# Digital_Interfaces.net
KiCad netlist of a schematic drawn in Altium Designer
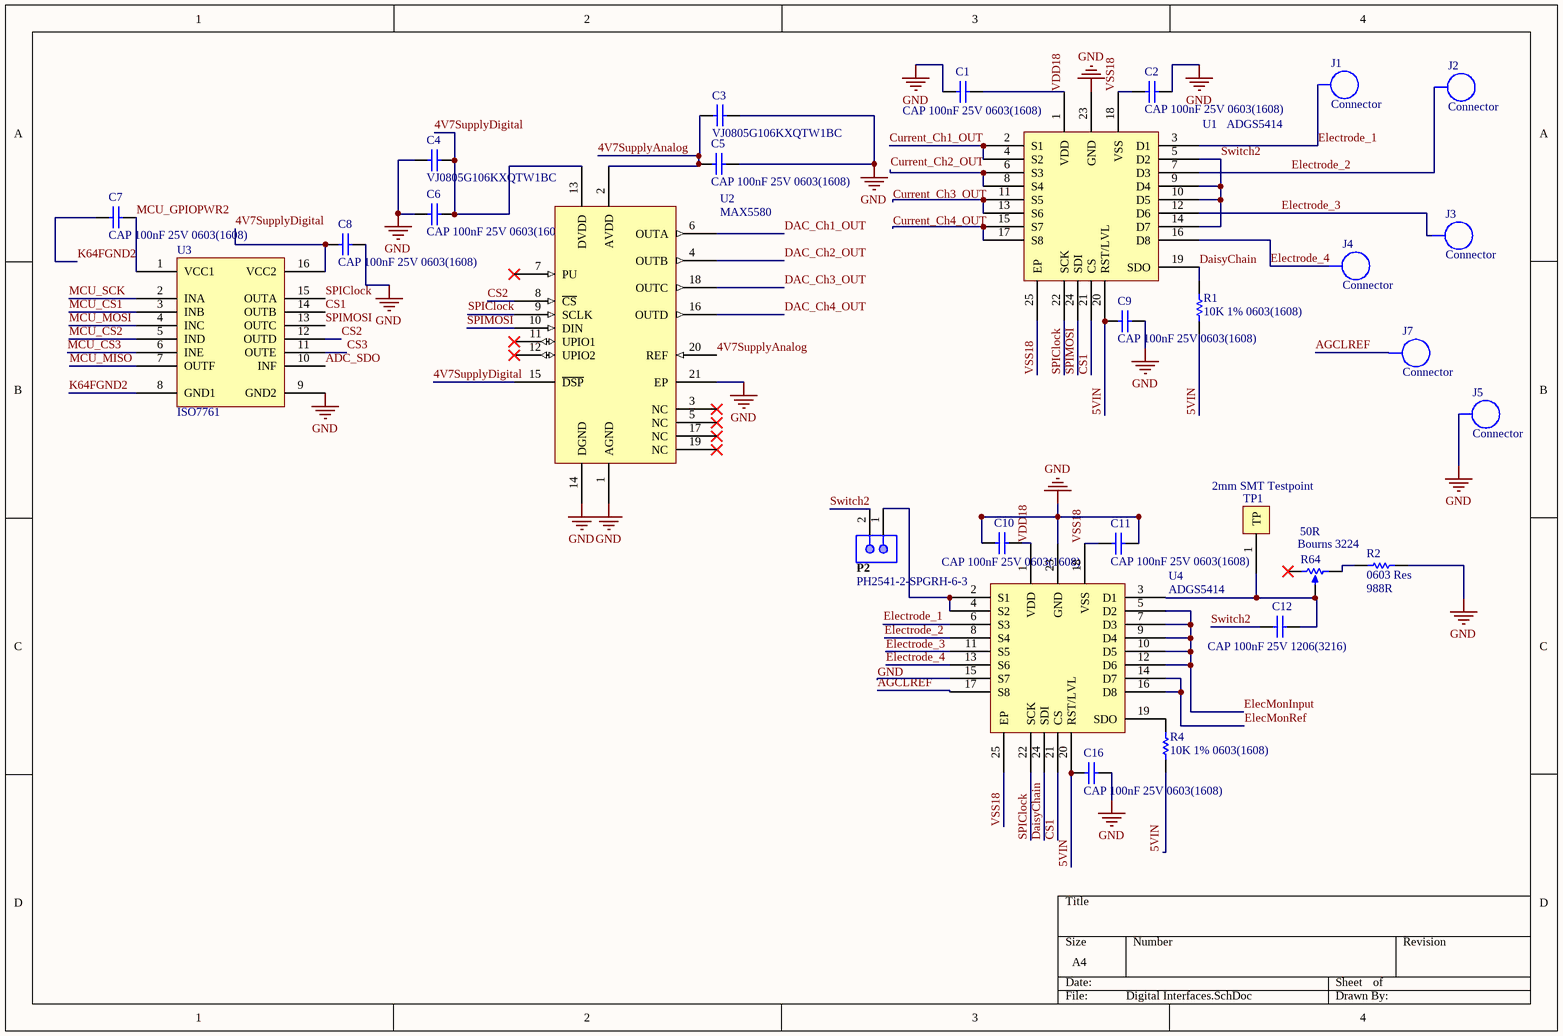
[diagram p0: Digital Interfaces.SchDoc]

(export (version "E")
  (design (tool "Eeschema 10.0.6"))
  (components
    (comp (ref "C1")
      (value "CAP 100nF 25V 0603(1608)")
      (footprint "CAPC0603(1608)100_N")
      (description "CAP 100nF 25V ±20% 0603 (1608 Metric) Thickness 1mm SMD")
      (fields (field (name "TOLERANCE") "Â±20%"))
      (libsource (lib "Altium Content Vault") (part "CAP"))
    )
    (comp (ref "C2")
      (value "CAP 100nF 25V 0603(1608)")
      (footprint "CAPC0603(1608)100_N")
      (description "CAP 100nF 25V ±20% 0603 (1608 Metric) Thickness 1mm SMD")
      (fields (field (name "TOLERANCE") "Â±20%"))
      (libsource (lib "Altium Content Vault") (part "CAP"))
    )
    (comp (ref "C3")
      (value "VJ0805G106KXQTW1BC")
      (footprint "CAPC2013X145X50LL20T20")
      (description "Chip Capacitor, 10 uF, +/- 10%, 10 V, -55 to 85 degC, 0805 (2012 Metric), RoHS, Tape and Reel")
      (fields (field (name "MANUFACTURER") "Vishay") (field (name "TOLERANCE") "10%"))
      (libsource (lib "Altium Content Vault") (part "CAP-NP-2"))
    )
    (comp (ref "C4")
      (value "VJ0805G106KXQTW1BC")
      (footprint "CAPC2013X145X50LL20T20")
      (description "Chip Capacitor, 10 uF, +/- 10%, 10 V, -55 to 85 degC, 0805 (2012 Metric), RoHS, Tape and Reel")
      (fields (field (name "MANUFACTURER") "Vishay") (field (name "TOLERANCE") "10%"))
      (libsource (lib "Altium Content Vault") (part "CAP-NP-2"))
    )
    (comp (ref "C5")
      (value "CAP 100nF 25V 0603(1608)")
      (footprint "CAPC0603(1608)100_N")
      (description "CAP 100nF 25V ±20% 0603 (1608 Metric) Thickness 1mm SMD")
      (fields (field (name "TOLERANCE") "Â±20%"))
      (libsource (lib "Altium Content Vault") (part "CAP"))
    )
    (comp (ref "C6")
      (value "CAP 100nF 25V 0603(1608)")
      (footprint "CAPC0603(1608)100_N")
      (description "CAP 100nF 25V ±20% 0603 (1608 Metric) Thickness 1mm SMD")
      (fields (field (name "TOLERANCE") "Â±20%"))
      (libsource (lib "Altium Content Vault") (part "CAP"))
    )
    (comp (ref "C7")
      (value "CAP 100nF 25V 0603(1608)")
      (footprint "CAPC0603(1608)100_N")
      (description "CAP 100nF 25V ±20% 0603 (1608 Metric) Thickness 1mm SMD")
      (fields (field (name "TOLERANCE") "Â±20%"))
      (libsource (lib "Altium Content Vault") (part "CAP"))
    )
    (comp (ref "C8")
      (value "CAP 100nF 25V 0603(1608)")
      (footprint "CAPC0603(1608)100_N")
      (description "CAP 100nF 25V ±20% 0603 (1608 Metric) Thickness 1mm SMD")
      (fields (field (name "TOLERANCE") "Â±20%"))
      (libsource (lib "Altium Content Vault") (part "CAP"))
    )
    (comp (ref "C9")
      (value "CAP 100nF 25V 0603(1608)")
      (footprint "CAPC0603(1608)100_N")
      (description "CAP 100nF 25V ±20% 0603 (1608 Metric) Thickness 1mm SMD")
      (fields (field (name "TOLERANCE") "Â±20%"))
      (libsource (lib "Altium Content Vault") (part "CAP"))
    )
    (comp (ref "C10")
      (value "CAP 100nF 25V 0603(1608)")
      (footprint "CAPC0603(1608)100_N")
      (description "CAP 100nF 25V ±20% 0603 (1608 Metric) Thickness 1mm SMD")
      (fields (field (name "TOLERANCE") "Â±20%"))
      (libsource (lib "Altium Content Vault") (part "CAP"))
    )
    (comp (ref "C11")
      (value "CAP 100nF 25V 0603(1608)")
      (footprint "CAPC0603(1608)100_N")
      (description "CAP 100nF 25V ±20% 0603 (1608 Metric) Thickness 1mm SMD")
      (fields (field (name "TOLERANCE") "Â±20%"))
      (libsource (lib "Altium Content Vault") (part "CAP"))
    )
    (comp (ref "C12")
      (value "CAP 100nF 25V 1206(3216)")
      (footprint "CAPC1206(3216)190_M")
      (description "CAP 100nF 25V ±5% 1206 (3216 Metric) Thickness 1.9mm SMD")
      (fields (field (name "TOLERANCE") "Â±5%"))
      (libsource (lib "Altium Content Vault") (part "CAP"))
    )
    (comp (ref "C16")
      (value "CAP 100nF 25V 0603(1608)")
      (footprint "CAPC0603(1608)100_N")
      (description "CAP 100nF 25V ±20% 0603 (1608 Metric) Thickness 1mm SMD")
      (fields (field (name "TOLERANCE") "Â±20%"))
      (libsource (lib "Altium Content Vault") (part "CAP"))
    )
    (comp (ref "J1")
      (value "Connector")
      (footprint "Molex TermiMate Plug")
      (description "Molex TermiMate Plug/Receptacle, 1-way SMD Board to Board or Wire to Board Connector")
      (libsource (lib "ar5113_Altium_Library") (part "Molex TermiMate"))
    )
    (comp (ref "J2")
      (value "Connector")
      (footprint "Molex TermiMate Plug")
      (description "Molex TermiMate Plug/Receptacle, 1-way SMD Board to Board or Wire to Board Connector")
      (libsource (lib "ar5113_Altium_Library") (part "Molex TermiMate"))
    )
    (comp (ref "J3")
      (value "Connector")
      (footprint "Molex TermiMate Plug")
      (description "Molex TermiMate Plug/Receptacle, 1-way SMD Board to Board or Wire to Board Connector")
      (libsource (lib "ar5113_Altium_Library") (part "Molex TermiMate"))
    )
    (comp (ref "J4")
      (value "Connector")
      (footprint "Molex TermiMate Plug")
      (description "Molex TermiMate Plug/Receptacle, 1-way SMD Board to Board or Wire to Board Connector")
      (libsource (lib "ar5113_Altium_Library") (part "Molex TermiMate"))
    )
    (comp (ref "J5")
      (value "Connector")
      (footprint "Molex TermiMate Plug")
      (description "Molex TermiMate Plug/Receptacle, 1-way SMD Board to Board or Wire to Board Connector")
      (libsource (lib "ar5113_Altium_Library") (part "Molex TermiMate"))
    )
    (comp (ref "J7")
      (value "Connector")
      (footprint "Molex TermiMate Plug")
      (description "Molex TermiMate Plug/Receptacle, 1-way SMD Board to Board or Wire to Board Connector")
      (libsource (lib "ar5113_Altium_Library") (part "Molex TermiMate"))
    )
    (comp (ref "P2")
      (value "PH2541-2-SPGRH-6-3")
      (footprint "PH2541-2-SPGRH-6-3_V")
      (description "Male Header, Pitch 2.54mm, 2x1 Position, Mated Height 6mm, Tail Length 3mm")
      (libsource (lib "Altium Content Vault") (part "PCE-HDR-1P-M-R2"))
    )
    (comp (ref "R1")
      (value "10K 1% 0603(1608)")
      (footprint "RESC0603(1608)_N")
      (description "10K 0.1W 1% 0603 (1608 Metric)  SMD")
      (fields (field (name "POWER") "0.1 W") (field (name "TOLERANCE") "1 %"))
      (libsource (lib "Altium Content Vault") (part "RES"))
    )
    (comp (ref "R2")
      (value "0603 Res")
      (footprint "J1-0603")
      (description "Chip Resistor, 0603, 1%")
      (fields (field (name "ALTIUM_VALUE") "988R") (field (name "PUBLISHER") "Altium Limited"))
      (libsource (lib "Miscellaneous Devices") (part "Res1"))
    )
    (comp (ref "R4")
      (value "10K 1% 0603(1608)")
      (footprint "RESC0603(1608)_N")
      (description "10K 0.1W 1% 0603 (1608 Metric)  SMD")
      (fields (field (name "POWER") "0.1 W") (field (name "TOLERANCE") "1 %"))
      (libsource (lib "Altium Content Vault") (part "RES"))
    )
    (comp (ref "R64")
      (value "Bourns 3224")
      (footprint "BOURNS 3224W")
      (description "Trimmer Potentiometer, Cermet, 3224-Series (Bourns)")
      (fields (field (name "ALTIUM_VALUE") "50R") (field (name "PUBLISHER") "Altium Limited"))
      (libsource (lib "ar5113_Altium_Library") (part "3224-Series Trimmer Potentiometer"))
    )
    (comp (ref "TP1")
      (value "2mm SMT Testpoint")
      (footprint "Testpoint Harwin S1751")
      (description "SMT Testpoint, 2mm height, Harwin S1751")
      (libsource (lib "ar5113_Altium_Library") (part "TestPoint SMT Harwin S1751"))
    )
    (comp (ref "U1")
      (value "ADGS5414")
      (footprint "24LFCSP JEDEC MO-220-VGGD-8")
      (description "Octal ±20V SPST Switches, SPI interface, 13.5 ohm Ron, Break before Make")
      (libsource (lib "ar5113_Altium_Library") (part "ADGS5414"))
    )
    (comp (ref "U2")
      (value "MAX5580")
      (footprint "20TSSOP-EP U20E-1")
      (description "12-Bit Voltage DAC, 5.25V Single Supply, Buffered Fast-Settling, SPI input, Daisy Chainable")
      (libsource (lib "ar5113_Altium_Library") (part "MAX5580"))
    )
    (comp (ref "U3")
      (value "ISO7761")
      (footprint "16SSOP JEDEC MO-137 AB")
      (libsource (lib "ar5113_Altium_Library") (part "ISO7761"))
    )
    (comp (ref "U4")
      (value "ADGS5414")
      (footprint "24LFCSP JEDEC MO-220-VGGD-8")
      (description "Octal ±20V SPST Switches, SPI interface, 13.5 ohm Ron, Break before Make")
      (libsource (lib "ar5113_Altium_Library") (part "ADGS5414"))
    )
  )
  (nets
    (net (code "1") (name "/4V7SupplyAnalog") (class "Default")
      (node (ref "C3") (pin "1") (pinfunction "1_1") (pintype "passive"))
      (node (ref "C5") (pin "2") (pinfunction "2_2") (pintype "passive"))
      (node (ref "U2") (pin "2") (pinfunction "AVDD_2") (pintype "power_in"))
      (node (ref "U2") (pin "20") (pinfunction "REF_20") (pintype "input"))
    )
    (net (code "2") (name "/4V7SupplyDigital") (class "Default")
      (node (ref "C4") (pin "2") (pinfunction "2_2") (pintype "passive"))
      (node (ref "C6") (pin "1") (pinfunction "1_1") (pintype "passive"))
      (node (ref "C8") (pin "2") (pinfunction "2_2") (pintype "passive"))
      (node (ref "U2") (pin "13") (pinfunction "DVDD_13") (pintype "power_in"))
      (node (ref "U2") (pin "15") (pinfunction "~{DSP}_15") (pintype "passive"))
      (node (ref "U3") (pin "16") (pinfunction "VCC2_16") (pintype "passive"))
    )
    (net (code "3") (name "/5VIN") (class "Default")
      (node (ref "C16") (pin "2") (pinfunction "2_2") (pintype "passive"))
      (node (ref "C9") (pin "2") (pinfunction "2_2") (pintype "passive"))
      (node (ref "R1") (pin "1") (pinfunction "1_1") (pintype "passive"))
      (node (ref "R4") (pin "1") (pinfunction "1_1") (pintype "passive"))
      (node (ref "U1") (pin "20") (pinfunction "RST/LVL_20") (pintype "passive"))
      (node (ref "U4") (pin "20") (pinfunction "RST/LVL_20") (pintype "passive"))
    )
    (net (code "4") (name "/ADC_SDO") (class "Default")
      (node (ref "U3") (pin "10") (pinfunction "INF_10") (pintype "passive"))
    )
    (net (code "5") (name "/AGCLREF") (class "Default")
      (node (ref "J7") (pin "1") (pinfunction "1_1") (pintype "passive"))
      (node (ref "U4") (pin "17") (pinfunction "S8_17") (pintype "passive"))
    )
    (net (code "6") (name "/CS1") (class "Default")
      (node (ref "U1") (pin "21") (pinfunction "CS_21") (pintype "passive"))
      (node (ref "U3") (pin "14") (pinfunction "OUTB_14") (pintype "passive"))
      (node (ref "U4") (pin "21") (pinfunction "CS_21") (pintype "passive"))
    )
    (net (code "7") (name "/CS2") (class "Default")
      (node (ref "U2") (pin "8") (pinfunction "~{CS}_8") (pintype "input"))
      (node (ref "U3") (pin "12") (pinfunction "OUTD_12") (pintype "passive"))
    )
    (net (code "8") (name "/CS3") (class "Default")
      (node (ref "U3") (pin "11") (pinfunction "OUTE_11") (pintype "passive"))
    )
    (net (code "9") (name "/Current_Ch1_OUT") (class "Default")
      (node (ref "U1") (pin "2") (pinfunction "S1_2") (pintype "passive"))
      (node (ref "U1") (pin "4") (pinfunction "S2_4") (pintype "passive"))
    )
    (net (code "10") (name "/Current_Ch2_OUT") (class "Default")
      (node (ref "U1") (pin "6") (pinfunction "S3_6") (pintype "passive"))
      (node (ref "U1") (pin "8") (pinfunction "S4_8") (pintype "passive"))
    )
    (net (code "11") (name "/Current_Ch3_OUT") (class "Default")
      (node (ref "U1") (pin "11") (pinfunction "S5_11") (pintype "passive"))
      (node (ref "U1") (pin "13") (pinfunction "S6_13") (pintype "passive"))
    )
    (net (code "12") (name "/Current_Ch4_OUT") (class "Default")
      (node (ref "U1") (pin "15") (pinfunction "S7_15") (pintype "passive"))
      (node (ref "U1") (pin "17") (pinfunction "S8_17") (pintype "passive"))
    )
    (net (code "13") (name "/DAC_Ch1_OUT") (class "Default")
      (node (ref "U2") (pin "6") (pinfunction "OUTA_6") (pintype "output"))
    )
    (net (code "14") (name "/DAC_Ch2_OUT") (class "Default")
      (node (ref "U2") (pin "4") (pinfunction "OUTB_4") (pintype "output"))
    )
    (net (code "15") (name "/DAC_Ch3_OUT") (class "Default")
      (node (ref "U2") (pin "18") (pinfunction "OUTC_18") (pintype "output"))
    )
    (net (code "16") (name "/DAC_Ch4_OUT") (class "Default")
      (node (ref "U2") (pin "16") (pinfunction "OUTD_16") (pintype "output"))
    )
    (net (code "17") (name "/DaisyChain") (class "Default")
      (node (ref "R1") (pin "2") (pinfunction "2_2") (pintype "passive"))
      (node (ref "U1") (pin "19") (pinfunction "SDO_19") (pintype "passive"))
      (node (ref "U4") (pin "24") (pinfunction "SDI_24") (pintype "passive"))
    )
    (net (code "18") (name "/ElecMonInput") (class "Default")
      (node (ref "U4") (pin "10") (pinfunction "D5_10") (pintype "passive"))
      (node (ref "U4") (pin "12") (pinfunction "D6_12") (pintype "passive"))
      (node (ref "U4") (pin "5") (pinfunction "D2_5") (pintype "passive"))
      (node (ref "U4") (pin "7") (pinfunction "D3_7") (pintype "passive"))
      (node (ref "U4") (pin "9") (pinfunction "D4_9") (pintype "passive"))
    )
    (net (code "19") (name "/ElecMonRef") (class "Default")
      (node (ref "U4") (pin "14") (pinfunction "D7_14") (pintype "passive"))
      (node (ref "U4") (pin "16") (pinfunction "D8_16") (pintype "passive"))
    )
    (net (code "20") (name "/Electrode_1") (class "Default")
      (node (ref "J1") (pin "1") (pinfunction "1_1") (pintype "passive"))
      (node (ref "U1") (pin "3") (pinfunction "D1_3") (pintype "passive"))
      (node (ref "U4") (pin "6") (pinfunction "S3_6") (pintype "passive"))
    )
    (net (code "21") (name "/Electrode_2") (class "Default")
      (node (ref "J2") (pin "1") (pinfunction "1_1") (pintype "passive"))
      (node (ref "U1") (pin "7") (pinfunction "D3_7") (pintype "passive"))
      (node (ref "U4") (pin "8") (pinfunction "S4_8") (pintype "passive"))
    )
    (net (code "22") (name "/Electrode_3") (class "Default")
      (node (ref "J3") (pin "1") (pinfunction "1_1") (pintype "passive"))
      (node (ref "U1") (pin "12") (pinfunction "D6_12") (pintype "passive"))
      (node (ref "U4") (pin "11") (pinfunction "S5_11") (pintype "passive"))
    )
    (net (code "23") (name "/Electrode_4") (class "Default")
      (node (ref "J4") (pin "1") (pinfunction "1_1") (pintype "passive"))
      (node (ref "U1") (pin "16") (pinfunction "D8_16") (pintype "passive"))
      (node (ref "U4") (pin "13") (pinfunction "S6_13") (pintype "passive"))
    )
    (net (code "24") (name "/K64FGND2") (class "Default")
      (node (ref "C7") (pin "2") (pinfunction "2_2") (pintype "passive"))
      (node (ref "U3") (pin "8") (pinfunction "GND1_8") (pintype "passive"))
    )
    (net (code "25") (name "/MCU_CS1") (class "Default")
      (node (ref "U3") (pin "3") (pinfunction "INB_3") (pintype "passive"))
    )
    (net (code "26") (name "/MCU_CS2") (class "Default")
      (node (ref "U3") (pin "5") (pinfunction "IND_5") (pintype "passive"))
    )
    (net (code "27") (name "/MCU_CS3") (class "Default")
      (node (ref "U3") (pin "6") (pinfunction "INE_6") (pintype "passive"))
    )
    (net (code "28") (name "/MCU_GPIOPWR2") (class "Default")
      (node (ref "C7") (pin "1") (pinfunction "1_1") (pintype "passive"))
      (node (ref "U3") (pin "1") (pinfunction "VCC1_1") (pintype "passive"))
    )
    (net (code "29") (name "/MCU_MISO") (class "Default")
      (node (ref "U3") (pin "7") (pinfunction "OUTF_7") (pintype "passive"))
    )
    (net (code "30") (name "/MCU_MOSI") (class "Default")
      (node (ref "U3") (pin "4") (pinfunction "INC_4") (pintype "passive"))
    )
    (net (code "31") (name "/MCU_SCK") (class "Default")
      (node (ref "U3") (pin "2") (pinfunction "INA_2") (pintype "passive"))
    )
    (net (code "32") (name "/SPIClock") (class "Default")
      (node (ref "U1") (pin "22") (pinfunction "SCK_22") (pintype "passive"))
      (node (ref "U2") (pin "9") (pinfunction "SCLK_9") (pintype "input"))
      (node (ref "U3") (pin "15") (pinfunction "OUTA_15") (pintype "passive"))
      (node (ref "U4") (pin "22") (pinfunction "SCK_22") (pintype "passive"))
    )
    (net (code "33") (name "/SPIMOSI") (class "Default")
      (node (ref "U1") (pin "24") (pinfunction "SDI_24") (pintype "passive"))
      (node (ref "U2") (pin "10") (pinfunction "DIN_10") (pintype "input"))
      (node (ref "U3") (pin "13") (pinfunction "OUTC_13") (pintype "passive"))
    )
    (net (code "34") (name "/Switch2") (class "Default")
      (node (ref "C12") (pin "1") (pinfunction "1_1") (pintype "passive"))
      (node (ref "P2") (pin "2") (pinfunction "2_2") (pintype "passive"))
      (node (ref "U1") (pin "10") (pinfunction "D5_10") (pintype "passive"))
      (node (ref "U1") (pin "14") (pinfunction "D7_14") (pintype "passive"))
      (node (ref "U1") (pin "5") (pinfunction "D2_5") (pintype "passive"))
      (node (ref "U1") (pin "9") (pinfunction "D4_9") (pintype "passive"))
    )
    (net (code "35") (name "/VDD18") (class "Default")
      (node (ref "C1") (pin "2") (pinfunction "2_2") (pintype "passive"))
      (node (ref "C10") (pin "2") (pinfunction "2_2") (pintype "passive"))
      (node (ref "U1") (pin "1") (pinfunction "VDD_1") (pintype "passive"))
      (node (ref "U4") (pin "1") (pinfunction "VDD_1") (pintype "passive"))
    )
    (net (code "36") (name "/VSS18") (class "Default")
      (node (ref "C11") (pin "2") (pinfunction "2_2") (pintype "passive"))
      (node (ref "C2") (pin "2") (pinfunction "2_2") (pintype "passive"))
      (node (ref "U1") (pin "18") (pinfunction "VSS_18") (pintype "passive"))
      (node (ref "U1") (pin "25") (pinfunction "EP_25") (pintype "passive"))
      (node (ref "U4") (pin "18") (pinfunction "VSS_18") (pintype "passive"))
      (node (ref "U4") (pin "25") (pinfunction "EP_25") (pintype "passive"))
    )
    (net (code "37") (name "GND") (class "Default")
      (node (ref "C1") (pin "1") (pinfunction "1_1") (pintype "passive"))
      (node (ref "C10") (pin "1") (pinfunction "1_1") (pintype "passive"))
      (node (ref "C11") (pin "1") (pinfunction "1_1") (pintype "passive"))
      (node (ref "C16") (pin "1") (pinfunction "1_1") (pintype "passive"))
      (node (ref "C2") (pin "1") (pinfunction "1_1") (pintype "passive"))
      (node (ref "C3") (pin "2") (pinfunction "2_2") (pintype "passive"))
      (node (ref "C4") (pin "1") (pinfunction "1_1") (pintype "passive"))
      (node (ref "C5") (pin "1") (pinfunction "1_1") (pintype "passive"))
      (node (ref "C6") (pin "2") (pinfunction "2_2") (pintype "passive"))
      (node (ref "C8") (pin "1") (pinfunction "1_1") (pintype "passive"))
      (node (ref "C9") (pin "1") (pinfunction "1_1") (pintype "passive"))
      (node (ref "J5") (pin "1") (pinfunction "1_1") (pintype "passive"))
      (node (ref "R2") (pin "1") (pinfunction "1_1") (pintype "passive"))
      (node (ref "U1") (pin "23") (pinfunction "GND_23") (pintype "passive"))
      (node (ref "U2") (pin "1") (pinfunction "AGND_1") (pintype "power_in"))
      (node (ref "U2") (pin "14") (pinfunction "DGND_14") (pintype "power_in"))
      (node (ref "U2") (pin "21") (pinfunction "EP_21") (pintype "power_in"))
      (node (ref "U3") (pin "9") (pinfunction "GND2_9") (pintype "passive"))
      (node (ref "U4") (pin "15") (pinfunction "S7_15") (pintype "passive"))
      (node (ref "U4") (pin "23") (pinfunction "GND_23") (pintype "passive"))
    )
    (net (code "38") (name "Net-(R64-BOT)") (class "Default")
      (node (ref "R2") (pin "2") (pinfunction "2_2") (pintype "passive"))
      (node (ref "R64") (pin "3") (pinfunction "BOT_3") (pintype "passive"))
    )
    (net (code "39") (name "Net-(R64-TAP)") (class "Default")
      (node (ref "C12") (pin "2") (pinfunction "2_2") (pintype "passive"))
      (node (ref "R64") (pin "2") (pinfunction "TAP_2") (pintype "passive"))
      (node (ref "TP1") (pin "1") (pinfunction "TP_1") (pintype "passive"))
      (node (ref "U4") (pin "3") (pinfunction "D1_3") (pintype "passive"))
    )
    (net (code "40") (name "Net-(U4-S1)") (class "Default")
      (node (ref "P2") (pin "1") (pinfunction "1_1") (pintype "passive"))
      (node (ref "U4") (pin "2") (pinfunction "S1_2") (pintype "passive"))
      (node (ref "U4") (pin "4") (pinfunction "S2_4") (pintype "passive"))
    )
    (net (code "41") (name "Net-(U4-SDO)") (class "Default")
      (node (ref "R4") (pin "2") (pinfunction "2_2") (pintype "passive"))
      (node (ref "U4") (pin "19") (pinfunction "SDO_19") (pintype "passive"))
    )
    (net (code "42") (name "unconnected-(R64-TOP-Pad1)") (class "Default")
      (node (ref "R64") (pin "1") (pinfunction "TOP_1") (pintype "passive+no_connect"))
    )
    (net (code "43") (name "unconnected-(U2-NC-Pad3)") (class "Default")
      (node (ref "U2") (pin "3") (pinfunction "NC_3") (pintype "passive+no_connect"))
    )
    (net (code "44") (name "unconnected-(U2-NC-Pad5)") (class "Default")
      (node (ref "U2") (pin "5") (pinfunction "NC_5") (pintype "passive+no_connect"))
    )
    (net (code "45") (name "unconnected-(U2-NC-Pad17)") (class "Default")
      (node (ref "U2") (pin "17") (pinfunction "NC_17") (pintype "passive+no_connect"))
    )
    (net (code "46") (name "unconnected-(U2-NC-Pad19)") (class "Default")
      (node (ref "U2") (pin "19") (pinfunction "NC_19") (pintype "passive+no_connect"))
    )
    (net (code "47") (name "unconnected-(U2-PU-Pad7)") (class "Default")
      (node (ref "U2") (pin "7") (pinfunction "PU_7") (pintype "input+no_connect"))
    )
    (net (code "48") (name "unconnected-(U2-UPIO1-Pad11)") (class "Default")
      (node (ref "U2") (pin "11") (pinfunction "UPIO1_11") (pintype "bidirectional+no_connect"))
    )
    (net (code "49") (name "unconnected-(U2-UPIO2-Pad12)") (class "Default")
      (node (ref "U2") (pin "12") (pinfunction "UPIO2_12") (pintype "bidirectional+no_connect"))
    )
  )
)
